# ArachnoMoto.net
KiCad netlist of a schematic drawn in EAGLE
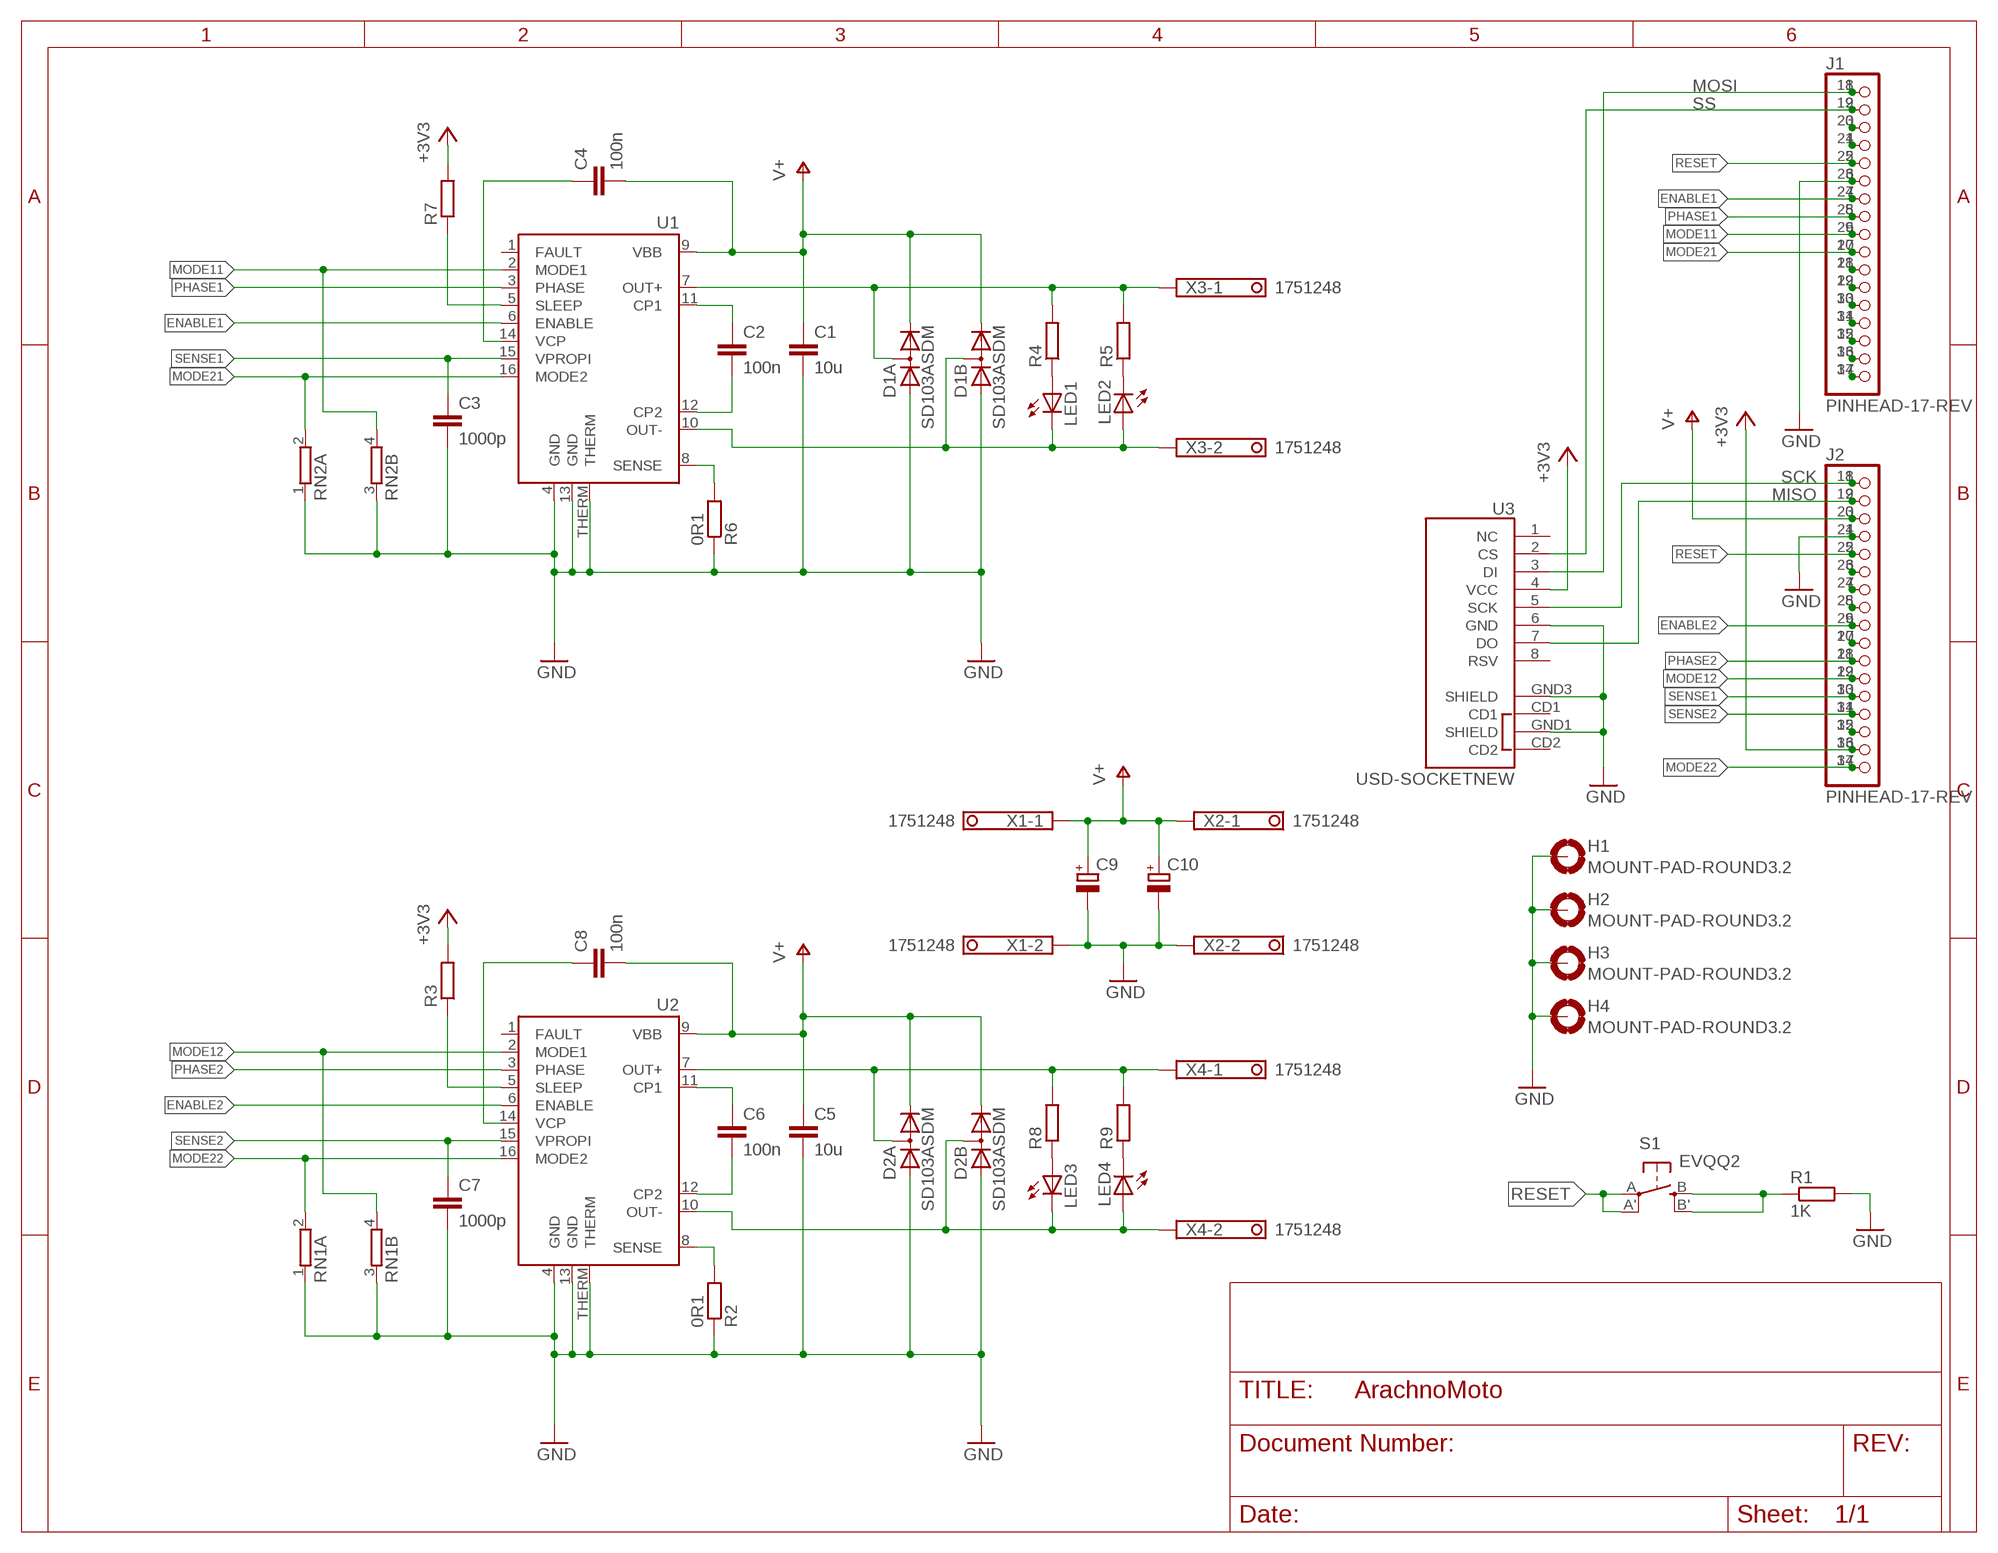
[diagram p0: schematic, sheet 1]

(export (version "E")
  (design (tool "Eeschema 10.0.6"))
  (components
    (comp (ref "C1")
      (value "10u")
      (footprint "eagle-import:C1210")
      (libsource (lib "eagle-import") (part "C-EUC1210"))
    )
    (comp (ref "C2")
      (value "100n")
      (footprint "eagle-import:C0603")
      (libsource (lib "eagle-import") (part "C-EUC0603"))
    )
    (comp (ref "C3")
      (value "1000p")
      (footprint "eagle-import:C0603")
      (libsource (lib "eagle-import") (part "C-EUC0603"))
    )
    (comp (ref "C4")
      (value "100n")
      (footprint "eagle-import:C0603")
      (libsource (lib "eagle-import") (part "C-EUC0603"))
    )
    (comp (ref "C5")
      (value "10u")
      (footprint "eagle-import:C1210")
      (libsource (lib "eagle-import") (part "C-EUC1210"))
    )
    (comp (ref "C6")
      (value "100n")
      (footprint "eagle-import:C0603")
      (libsource (lib "eagle-import") (part "C-EUC0603"))
    )
    (comp (ref "C7")
      (value "1000p")
      (footprint "eagle-import:C0603")
      (libsource (lib "eagle-import") (part "C-EUC0603"))
    )
    (comp (ref "C8")
      (value "100n")
      (footprint "eagle-import:C0603")
      (libsource (lib "eagle-import") (part "C-EUC0603"))
    )
    (comp (ref "C9")
      (value "CPOL-EUE5-10.5")
      (footprint "eagle-import:E5-10,5")
      (libsource (lib "eagle-import") (part "CPOL-EUE5-10.5"))
    )
    (comp (ref "C10")
      (value "CPOL-EUE5-10.5")
      (footprint "eagle-import:E5-10,5")
      (libsource (lib "eagle-import") (part "CPOL-EUE5-10.5"))
    )
    (comp (ref "D1")
      (value "SD103ASDM")
      (footprint "eagle-import:SOT26")
      (libsource (lib "eagle-import") (part "SD103ASDM"))
    )
    (comp (ref "D2")
      (value "SD103ASDM")
      (footprint "eagle-import:SOT26")
      (libsource (lib "eagle-import") (part "SD103ASDM"))
    )
    (comp (ref "H1")
      (value "MOUNT-PAD-ROUND3.2")
      (footprint "eagle-import:3,2-PAD")
      (libsource (lib "eagle-import") (part "MOUNT-PAD-ROUND3.2"))
    )
    (comp (ref "H2")
      (value "MOUNT-PAD-ROUND3.2")
      (footprint "eagle-import:3,2-PAD")
      (libsource (lib "eagle-import") (part "MOUNT-PAD-ROUND3.2"))
    )
    (comp (ref "H3")
      (value "MOUNT-PAD-ROUND3.2")
      (footprint "eagle-import:3,2-PAD")
      (libsource (lib "eagle-import") (part "MOUNT-PAD-ROUND3.2"))
    )
    (comp (ref "H4")
      (value "MOUNT-PAD-ROUND3.2")
      (footprint "eagle-import:3,2-PAD")
      (libsource (lib "eagle-import") (part "MOUNT-PAD-ROUND3.2"))
    )
    (comp (ref "J1")
      (value "PINHEAD-17-REV")
      (footprint "eagle-import:4UCONN-12573")
      (libsource (lib "eagle-import") (part "PINHEAD-17-REV"))
    )
    (comp (ref "J2")
      (value "PINHEAD-17-REV")
      (footprint "eagle-import:4UCONN-12573")
      (libsource (lib "eagle-import") (part "PINHEAD-17-REV"))
    )
    (comp (ref "LED1")
      (value "LEDCHIP-LED0603")
      (footprint "eagle-import:CHIP-LED0603")
      (libsource (lib "eagle-import") (part "LEDCHIP-LED0603"))
    )
    (comp (ref "LED2")
      (value "LEDCHIP-LED0603")
      (footprint "eagle-import:CHIP-LED0603")
      (libsource (lib "eagle-import") (part "LEDCHIP-LED0603"))
    )
    (comp (ref "LED3")
      (value "LEDCHIP-LED0603")
      (footprint "eagle-import:CHIP-LED0603")
      (libsource (lib "eagle-import") (part "LEDCHIP-LED0603"))
    )
    (comp (ref "LED4")
      (value "LEDCHIP-LED0603")
      (footprint "eagle-import:CHIP-LED0603")
      (libsource (lib "eagle-import") (part "LEDCHIP-LED0603"))
    )
    (comp (ref "R1")
      (value "1K")
      (footprint "eagle-import:R1206")
      (libsource (lib "eagle-import") (part "R-EU_R1206"))
    )
    (comp (ref "R2")
      (value "0R1")
      (footprint "eagle-import:R1206")
      (libsource (lib "eagle-import") (part "R-EU_R1206"))
    )
    (comp (ref "R3")
      (value "R-EU_R0603")
      (footprint "eagle-import:R0603")
      (libsource (lib "eagle-import") (part "R-EU_R0603"))
    )
    (comp (ref "R4")
      (value "R-EU_R0603")
      (footprint "eagle-import:R0603")
      (libsource (lib "eagle-import") (part "R-EU_R0603"))
    )
    (comp (ref "R5")
      (value "R-EU_R0603")
      (footprint "eagle-import:R0603")
      (libsource (lib "eagle-import") (part "R-EU_R0603"))
    )
    (comp (ref "R6")
      (value "0R1")
      (footprint "eagle-import:R1206")
      (libsource (lib "eagle-import") (part "R-EU_R1206"))
    )
    (comp (ref "R7")
      (value "R-EU_R0603")
      (footprint "eagle-import:R0603")
      (libsource (lib "eagle-import") (part "R-EU_R0603"))
    )
    (comp (ref "R8")
      (value "R-EU_R0603")
      (footprint "eagle-import:R0603")
      (libsource (lib "eagle-import") (part "R-EU_R0603"))
    )
    (comp (ref "R9")
      (value "R-EU_R0603")
      (footprint "eagle-import:R0603")
      (libsource (lib "eagle-import") (part "R-EU_R0603"))
    )
    (comp (ref "RN1")
      (value "4R-NCTS742C083")
      (footprint "eagle-import:CTS742C083-RES")
      (libsource (lib "eagle-import") (part "4R-NCTS742C083"))
    )
    (comp (ref "RN2")
      (value "4R-NCTS742C083")
      (footprint "eagle-import:CTS742C083-RES")
      (libsource (lib "eagle-import") (part "4R-NCTS742C083"))
    )
    (comp (ref "S1")
      (value "EVQQ2")
      (footprint "eagle-import:EVQ-Q2")
      (libsource (lib "eagle-import") (part "EVQQ2"))
    )
    (comp (ref "U1")
      (value "DRV8801")
      (footprint "eagle-import:HTSSOP16-PWP")
      (libsource (lib "eagle-import") (part "DRV8801"))
    )
    (comp (ref "U2")
      (value "DRV8801")
      (footprint "eagle-import:HTSSOP16-PWP")
      (libsource (lib "eagle-import") (part "DRV8801"))
    )
    (comp (ref "U3")
      (value "USD-SOCKETNEW")
      (footprint "eagle-import:MICRO-SD-SOCKET-PP")
      (libsource (lib "eagle-import") (part "USD-SOCKETNEW"))
    )
    (comp (ref "X1")
      (value "1751248")
      (footprint "eagle-import:1751248")
      (libsource (lib "eagle-import") (part "1751248"))
    )
    (comp (ref "X2")
      (value "1751248")
      (footprint "eagle-import:1751248")
      (libsource (lib "eagle-import") (part "1751248"))
    )
    (comp (ref "X3")
      (value "1751248")
      (footprint "eagle-import:1751248")
      (libsource (lib "eagle-import") (part "1751248"))
    )
    (comp (ref "X4")
      (value "1751248")
      (footprint "eagle-import:1751248")
      (libsource (lib "eagle-import") (part "1751248"))
    )
  )
  (nets
    (net (code "1") (name "+3V3") (class "Default")
      (node (ref "J2") (pin "16") (pinfunction "16_16") (pintype "passive"))
      (node (ref "J2") (pin "33") (pinfunction "33_33") (pintype "passive"))
      (node (ref "R3") (pin "2") (pinfunction "2_2") (pintype "passive"))
      (node (ref "R7") (pin "2") (pinfunction "2_2") (pintype "passive"))
      (node (ref "U3") (pin "4") (pinfunction "VCC_4") (pintype "bidirectional"))
    )
    (net (code "2") (name "/MISO") (class "Default")
      (node (ref "J2") (pin "19") (pinfunction "19_19") (pintype "passive"))
      (node (ref "J2") (pin "2") (pinfunction "2_2") (pintype "passive"))
      (node (ref "U3") (pin "7") (pinfunction "DO_7") (pintype "bidirectional"))
    )
    (net (code "3") (name "/MOSI") (class "Default")
      (node (ref "J1") (pin "1") (pinfunction "1_1") (pintype "passive"))
      (node (ref "J1") (pin "18") (pinfunction "18_18") (pintype "passive"))
      (node (ref "U3") (pin "3") (pinfunction "DI_3") (pintype "bidirectional"))
    )
    (net (code "4") (name "/SCK") (class "Default")
      (node (ref "J2") (pin "1") (pinfunction "1_1") (pintype "passive"))
      (node (ref "J2") (pin "18") (pinfunction "18_18") (pintype "passive"))
      (node (ref "U3") (pin "5") (pinfunction "SCK_5") (pintype "bidirectional"))
    )
    (net (code "5") (name "/SS") (class "Default")
      (node (ref "J1") (pin "19") (pinfunction "19_19") (pintype "passive"))
      (node (ref "J1") (pin "2") (pinfunction "2_2") (pintype "passive"))
      (node (ref "U3") (pin "2") (pinfunction "CS_2") (pintype "bidirectional"))
    )
    (net (code "6") (name "ENABLE1") (class "Default")
      (node (ref "J1") (pin "24") (pinfunction "24_24") (pintype "passive"))
      (node (ref "J1") (pin "7") (pinfunction "7_7") (pintype "passive"))
      (node (ref "U1") (pin "6") (pinfunction "ENABLE_6") (pintype "bidirectional"))
    )
    (net (code "7") (name "ENABLE2") (class "Default")
      (node (ref "J2") (pin "26") (pinfunction "26_26") (pintype "passive"))
      (node (ref "J2") (pin "9") (pinfunction "9_9") (pintype "passive"))
      (node (ref "U2") (pin "6") (pinfunction "ENABLE_6") (pintype "bidirectional"))
    )
    (net (code "8") (name "GND") (class "Default")
      (node (ref "C1") (pin "2") (pinfunction "2_2") (pintype "passive"))
      (node (ref "C10") (pin "-") (pinfunction "-_-") (pintype "passive"))
      (node (ref "C3") (pin "2") (pinfunction "2_2") (pintype "passive"))
      (node (ref "C5") (pin "2") (pinfunction "2_2") (pintype "passive"))
      (node (ref "C7") (pin "2") (pinfunction "2_2") (pintype "passive"))
      (node (ref "C9") (pin "-") (pinfunction "-_-") (pintype "passive"))
      (node (ref "D1") (pin "3") (pinfunction "A_3") (pintype "passive"))
      (node (ref "D1") (pin "6") (pinfunction "A_6") (pintype "passive"))
      (node (ref "D2") (pin "3") (pinfunction "A_3") (pintype "passive"))
      (node (ref "D2") (pin "6") (pinfunction "A_6") (pintype "passive"))
      (node (ref "H1") (pin "B3,2") (pinfunction "MOUNT_B3,2") (pintype "passive"))
      (node (ref "H2") (pin "B3,2") (pinfunction "MOUNT_B3,2") (pintype "passive"))
      (node (ref "H3") (pin "B3,2") (pinfunction "MOUNT_B3,2") (pintype "passive"))
      (node (ref "H4") (pin "B3,2") (pinfunction "MOUNT_B3,2") (pintype "passive"))
      (node (ref "J1") (pin "23") (pinfunction "23_23") (pintype "passive"))
      (node (ref "J1") (pin "6") (pinfunction "6_6") (pintype "passive"))
      (node (ref "J2") (pin "21") (pinfunction "21_21") (pintype "passive"))
      (node (ref "J2") (pin "4") (pinfunction "4_4") (pintype "passive"))
      (node (ref "R1") (pin "2") (pinfunction "2_2") (pintype "passive"))
      (node (ref "R2") (pin "1") (pinfunction "1_1") (pintype "passive"))
      (node (ref "R6") (pin "1") (pinfunction "1_1") (pintype "passive"))
      (node (ref "RN1") (pin "1") (pinfunction "1_1") (pintype "passive"))
      (node (ref "RN1") (pin "3") (pinfunction "1_3") (pintype "passive"))
      (node (ref "RN2") (pin "1") (pinfunction "1_1") (pintype "passive"))
      (node (ref "RN2") (pin "3") (pinfunction "1_3") (pintype "passive"))
      (node (ref "U1") (pin "13") (pinfunction "GND_13") (pintype "bidirectional"))
      (node (ref "U1") (pin "4") (pinfunction "GND_4") (pintype "bidirectional"))
      (node (ref "U1") (pin "THERM") (pinfunction "THERM_THERM") (pintype "bidirectional"))
      (node (ref "U2") (pin "13") (pinfunction "GND_13") (pintype "bidirectional"))
      (node (ref "U2") (pin "4") (pinfunction "GND_4") (pintype "bidirectional"))
      (node (ref "U2") (pin "THERM") (pinfunction "THERM_THERM") (pintype "bidirectional"))
      (node (ref "U3") (pin "6") (pinfunction "GND_6") (pintype "bidirectional"))
      (node (ref "U3") (pin "GND1") (pinfunction "SHIELD_GND1") (pintype "bidirectional"))
      (node (ref "U3") (pin "GND3") (pinfunction "SHIELD_GND3") (pintype "bidirectional"))
      (node (ref "X1") (pin "2") (pinfunction "K_2") (pintype "passive"))
      (node (ref "X2") (pin "2") (pinfunction "K_2") (pintype "passive"))
    )
    (net (code "9") (name "MODE11") (class "Default")
      (node (ref "J1") (pin "26") (pinfunction "26_26") (pintype "passive"))
      (node (ref "J1") (pin "9") (pinfunction "9_9") (pintype "passive"))
      (node (ref "RN2") (pin "4") (pinfunction "2_4") (pintype "passive"))
      (node (ref "U1") (pin "2") (pinfunction "MODE1_2") (pintype "bidirectional"))
    )
    (net (code "10") (name "MODE12") (class "Default")
      (node (ref "J2") (pin "12") (pinfunction "12_12") (pintype "passive"))
      (node (ref "J2") (pin "29") (pinfunction "29_29") (pintype "passive"))
      (node (ref "RN1") (pin "4") (pinfunction "2_4") (pintype "passive"))
      (node (ref "U2") (pin "2") (pinfunction "MODE1_2") (pintype "bidirectional"))
    )
    (net (code "11") (name "MODE21") (class "Default")
      (node (ref "J1") (pin "10") (pinfunction "10_10") (pintype "passive"))
      (node (ref "J1") (pin "27") (pinfunction "27_27") (pintype "passive"))
      (node (ref "RN2") (pin "2") (pinfunction "2_2") (pintype "passive"))
      (node (ref "U1") (pin "16") (pinfunction "MODE2_16") (pintype "bidirectional"))
    )
    (net (code "12") (name "MODE22") (class "Default")
      (node (ref "J2") (pin "17") (pinfunction "17_17") (pintype "passive"))
      (node (ref "J2") (pin "34") (pinfunction "34_34") (pintype "passive"))
      (node (ref "RN1") (pin "2") (pinfunction "2_2") (pintype "passive"))
      (node (ref "U2") (pin "16") (pinfunction "MODE2_16") (pintype "bidirectional"))
    )
    (net (code "13") (name "Net-(D1A-AC)") (class "Default")
      (node (ref "D1") (pin "4") (pinfunction "AC_4") (pintype "passive"))
      (node (ref "R4") (pin "2") (pinfunction "2_2") (pintype "passive"))
      (node (ref "R5") (pin "2") (pinfunction "2_2") (pintype "passive"))
      (node (ref "U1") (pin "7") (pinfunction "OUT+_7") (pintype "bidirectional"))
      (node (ref "X3") (pin "1") (pinfunction "K_1") (pintype "passive"))
    )
    (net (code "14") (name "Net-(D1B-AC)") (class "Default")
      (node (ref "D1") (pin "1") (pinfunction "AC_1") (pintype "passive"))
      (node (ref "LED1") (pin "C") (pinfunction "C_C") (pintype "passive"))
      (node (ref "LED2") (pin "A") (pinfunction "A_A") (pintype "passive"))
      (node (ref "U1") (pin "10") (pinfunction "OUT-_10") (pintype "bidirectional"))
      (node (ref "X3") (pin "2") (pinfunction "K_2") (pintype "passive"))
    )
    (net (code "15") (name "Net-(D2A-AC)") (class "Default")
      (node (ref "D2") (pin "4") (pinfunction "AC_4") (pintype "passive"))
      (node (ref "R8") (pin "2") (pinfunction "2_2") (pintype "passive"))
      (node (ref "R9") (pin "2") (pinfunction "2_2") (pintype "passive"))
      (node (ref "U2") (pin "7") (pinfunction "OUT+_7") (pintype "bidirectional"))
      (node (ref "X4") (pin "1") (pinfunction "K_1") (pintype "passive"))
    )
    (net (code "16") (name "Net-(D2B-AC)") (class "Default")
      (node (ref "D2") (pin "1") (pinfunction "AC_1") (pintype "passive"))
      (node (ref "LED3") (pin "C") (pinfunction "C_C") (pintype "passive"))
      (node (ref "LED4") (pin "A") (pinfunction "A_A") (pintype "passive"))
      (node (ref "U2") (pin "10") (pinfunction "OUT-_10") (pintype "bidirectional"))
      (node (ref "X4") (pin "2") (pinfunction "K_2") (pintype "passive"))
    )
    (net (code "17") (name "Net-(J1-Pad11)") (class "Default")
      (node (ref "J1") (pin "11") (pinfunction "11_11") (pintype "passive"))
      (node (ref "J1") (pin "28") (pinfunction "28_28") (pintype "passive"))
    )
    (net (code "18") (name "Net-(J1-Pad12)") (class "Default")
      (node (ref "J1") (pin "12") (pinfunction "12_12") (pintype "passive"))
      (node (ref "J1") (pin "29") (pinfunction "29_29") (pintype "passive"))
    )
    (net (code "19") (name "Net-(J1-Pad13)") (class "Default")
      (node (ref "J1") (pin "13") (pinfunction "13_13") (pintype "passive"))
      (node (ref "J1") (pin "30") (pinfunction "30_30") (pintype "passive"))
    )
    (net (code "20") (name "Net-(J1-Pad14)") (class "Default")
      (node (ref "J1") (pin "14") (pinfunction "14_14") (pintype "passive"))
      (node (ref "J1") (pin "31") (pinfunction "31_31") (pintype "passive"))
    )
    (net (code "21") (name "Net-(J1-Pad15)") (class "Default")
      (node (ref "J1") (pin "15") (pinfunction "15_15") (pintype "passive"))
      (node (ref "J1") (pin "32") (pinfunction "32_32") (pintype "passive"))
    )
    (net (code "22") (name "Net-(J1-Pad16)") (class "Default")
      (node (ref "J1") (pin "16") (pinfunction "16_16") (pintype "passive"))
      (node (ref "J1") (pin "33") (pinfunction "33_33") (pintype "passive"))
    )
    (net (code "23") (name "Net-(J1-Pad17)") (class "Default")
      (node (ref "J1") (pin "17") (pinfunction "17_17") (pintype "passive"))
      (node (ref "J1") (pin "34") (pinfunction "34_34") (pintype "passive"))
    )
    (net (code "24") (name "Net-(J1-Pad20)") (class "Default")
      (node (ref "J1") (pin "20") (pinfunction "20_20") (pintype "passive"))
      (node (ref "J1") (pin "3") (pinfunction "3_3") (pintype "passive"))
    )
    (net (code "25") (name "Net-(J1-Pad21)") (class "Default")
      (node (ref "J1") (pin "21") (pinfunction "21_21") (pintype "passive"))
      (node (ref "J1") (pin "4") (pinfunction "4_4") (pintype "passive"))
    )
    (net (code "26") (name "Net-(J2-Pad10)") (class "Default")
      (node (ref "J2") (pin "10") (pinfunction "10_10") (pintype "passive"))
      (node (ref "J2") (pin "27") (pinfunction "27_27") (pintype "passive"))
    )
    (net (code "27") (name "Net-(J2-Pad15)") (class "Default")
      (node (ref "J2") (pin "15") (pinfunction "15_15") (pintype "passive"))
      (node (ref "J2") (pin "32") (pinfunction "32_32") (pintype "passive"))
    )
    (net (code "28") (name "Net-(J2-Pad23)") (class "Default")
      (node (ref "J2") (pin "23") (pinfunction "23_23") (pintype "passive"))
      (node (ref "J2") (pin "6") (pinfunction "6_6") (pintype "passive"))
    )
    (net (code "29") (name "Net-(J2-Pad24)") (class "Default")
      (node (ref "J2") (pin "24") (pinfunction "24_24") (pintype "passive"))
      (node (ref "J2") (pin "7") (pinfunction "7_7") (pintype "passive"))
    )
    (net (code "30") (name "Net-(J2-Pad25)") (class "Default")
      (node (ref "J2") (pin "25") (pinfunction "25_25") (pintype "passive"))
      (node (ref "J2") (pin "8") (pinfunction "8_8") (pintype "passive"))
    )
    (net (code "31") (name "Net-(LED1-PadA)") (class "Default")
      (node (ref "LED1") (pin "A") (pinfunction "A_A") (pintype "passive"))
      (node (ref "R4") (pin "1") (pinfunction "1_1") (pintype "passive"))
    )
    (net (code "32") (name "Net-(LED2-PadC)") (class "Default")
      (node (ref "LED2") (pin "C") (pinfunction "C_C") (pintype "passive"))
      (node (ref "R5") (pin "1") (pinfunction "1_1") (pintype "passive"))
    )
    (net (code "33") (name "Net-(LED3-PadA)") (class "Default")
      (node (ref "LED3") (pin "A") (pinfunction "A_A") (pintype "passive"))
      (node (ref "R8") (pin "1") (pinfunction "1_1") (pintype "passive"))
    )
    (net (code "34") (name "Net-(LED4-PadC)") (class "Default")
      (node (ref "LED4") (pin "C") (pinfunction "C_C") (pintype "passive"))
      (node (ref "R9") (pin "1") (pinfunction "1_1") (pintype "passive"))
    )
    (net (code "35") (name "Net-(S1-S)") (class "Default")
      (node (ref "R1") (pin "1") (pinfunction "1_1") (pintype "passive"))
      (node (ref "S1") (pin "B") (pinfunction "S_B") (pintype "passive"))
      (node (ref "S1") (pin "B'") (pinfunction "S1_B'") (pintype "passive"))
    )
    (net (code "36") (name "Net-(U1-CP1)") (class "Default")
      (node (ref "C2") (pin "1") (pinfunction "1_1") (pintype "passive"))
      (node (ref "U1") (pin "11") (pinfunction "CP1_11") (pintype "bidirectional"))
    )
    (net (code "37") (name "Net-(U1-CP2)") (class "Default")
      (node (ref "C2") (pin "2") (pinfunction "2_2") (pintype "passive"))
      (node (ref "U1") (pin "12") (pinfunction "CP2_12") (pintype "bidirectional"))
    )
    (net (code "38") (name "Net-(U1-SENSE)") (class "Default")
      (node (ref "R6") (pin "2") (pinfunction "2_2") (pintype "passive"))
      (node (ref "U1") (pin "8") (pinfunction "SENSE_8") (pintype "bidirectional"))
    )
    (net (code "39") (name "Net-(U1-SLEEP)") (class "Default")
      (node (ref "R7") (pin "1") (pinfunction "1_1") (pintype "passive"))
      (node (ref "U1") (pin "5") (pinfunction "SLEEP_5") (pintype "bidirectional"))
    )
    (net (code "40") (name "Net-(U1-VCP)") (class "Default")
      (node (ref "C4") (pin "1") (pinfunction "1_1") (pintype "passive"))
      (node (ref "U1") (pin "14") (pinfunction "VCP_14") (pintype "bidirectional"))
    )
    (net (code "41") (name "Net-(U2-CP1)") (class "Default")
      (node (ref "C6") (pin "1") (pinfunction "1_1") (pintype "passive"))
      (node (ref "U2") (pin "11") (pinfunction "CP1_11") (pintype "bidirectional"))
    )
    (net (code "42") (name "Net-(U2-CP2)") (class "Default")
      (node (ref "C6") (pin "2") (pinfunction "2_2") (pintype "passive"))
      (node (ref "U2") (pin "12") (pinfunction "CP2_12") (pintype "bidirectional"))
    )
    (net (code "43") (name "Net-(U2-SENSE)") (class "Default")
      (node (ref "R2") (pin "2") (pinfunction "2_2") (pintype "passive"))
      (node (ref "U2") (pin "8") (pinfunction "SENSE_8") (pintype "bidirectional"))
    )
    (net (code "44") (name "Net-(U2-SLEEP)") (class "Default")
      (node (ref "R3") (pin "1") (pinfunction "1_1") (pintype "passive"))
      (node (ref "U2") (pin "5") (pinfunction "SLEEP_5") (pintype "bidirectional"))
    )
    (net (code "45") (name "Net-(U2-VCP)") (class "Default")
      (node (ref "C8") (pin "1") (pinfunction "1_1") (pintype "passive"))
      (node (ref "U2") (pin "14") (pinfunction "VCP_14") (pintype "bidirectional"))
    )
    (net (code "46") (name "PHASE1") (class "Default")
      (node (ref "J1") (pin "25") (pinfunction "25_25") (pintype "passive"))
      (node (ref "J1") (pin "8") (pinfunction "8_8") (pintype "passive"))
      (node (ref "U1") (pin "3") (pinfunction "PHASE_3") (pintype "bidirectional"))
    )
    (net (code "47") (name "PHASE2") (class "Default")
      (node (ref "J2") (pin "11") (pinfunction "11_11") (pintype "passive"))
      (node (ref "J2") (pin "28") (pinfunction "28_28") (pintype "passive"))
      (node (ref "U2") (pin "3") (pinfunction "PHASE_3") (pintype "bidirectional"))
    )
    (net (code "48") (name "RESET") (class "Default")
      (node (ref "J1") (pin "22") (pinfunction "22_22") (pintype "passive"))
      (node (ref "J1") (pin "5") (pinfunction "5_5") (pintype "passive"))
      (node (ref "J2") (pin "22") (pinfunction "22_22") (pintype "passive"))
      (node (ref "J2") (pin "5") (pinfunction "5_5") (pintype "passive"))
      (node (ref "S1") (pin "A") (pinfunction "P_A") (pintype "passive"))
      (node (ref "S1") (pin "A'") (pinfunction "P1_A'") (pintype "passive"))
    )
    (net (code "49") (name "SENSE1") (class "Default")
      (node (ref "C3") (pin "1") (pinfunction "1_1") (pintype "passive"))
      (node (ref "J2") (pin "13") (pinfunction "13_13") (pintype "passive"))
      (node (ref "J2") (pin "30") (pinfunction "30_30") (pintype "passive"))
      (node (ref "U1") (pin "15") (pinfunction "VPROPI_15") (pintype "bidirectional"))
    )
    (net (code "50") (name "SENSE2") (class "Default")
      (node (ref "C7") (pin "1") (pinfunction "1_1") (pintype "passive"))
      (node (ref "J2") (pin "14") (pinfunction "14_14") (pintype "passive"))
      (node (ref "J2") (pin "31") (pinfunction "31_31") (pintype "passive"))
      (node (ref "U2") (pin "15") (pinfunction "VPROPI_15") (pintype "bidirectional"))
    )
    (net (code "51") (name "V+") (class "Default")
      (node (ref "C1") (pin "1") (pinfunction "1_1") (pintype "passive"))
      (node (ref "C10") (pin "+") (pinfunction "+_+") (pintype "passive"))
      (node (ref "C4") (pin "2") (pinfunction "2_2") (pintype "passive"))
      (node (ref "C5") (pin "1") (pinfunction "1_1") (pintype "passive"))
      (node (ref "C8") (pin "2") (pinfunction "2_2") (pintype "passive"))
      (node (ref "C9") (pin "+") (pinfunction "+_+") (pintype "passive"))
      (node (ref "D1") (pin "2") (pinfunction "C_2") (pintype "passive"))
      (node (ref "D1") (pin "5") (pinfunction "C_5") (pintype "passive"))
      (node (ref "D2") (pin "2") (pinfunction "C_2") (pintype "passive"))
      (node (ref "D2") (pin "5") (pinfunction "C_5") (pintype "passive"))
      (node (ref "J2") (pin "20") (pinfunction "20_20") (pintype "passive"))
      (node (ref "J2") (pin "3") (pinfunction "3_3") (pintype "passive"))
      (node (ref "U1") (pin "9") (pinfunction "VBB_9") (pintype "bidirectional"))
      (node (ref "U2") (pin "9") (pinfunction "VBB_9") (pintype "bidirectional"))
      (node (ref "X1") (pin "1") (pinfunction "K_1") (pintype "passive"))
      (node (ref "X2") (pin "1") (pinfunction "K_1") (pintype "passive"))
    )
    (net (code "52") (name "unconnected-(U1-FAULT-Pad1)") (class "Default")
      (node (ref "U1") (pin "1") (pinfunction "FAULT_1") (pintype "bidirectional"))
    )
    (net (code "53") (name "unconnected-(U2-FAULT-Pad1)") (class "Default")
      (node (ref "U2") (pin "1") (pinfunction "FAULT_1") (pintype "bidirectional"))
    )
    (net (code "54") (name "unconnected-(U3-NC-Pad1)") (class "Default")
      (node (ref "U3") (pin "1") (pinfunction "NC_1") (pintype "bidirectional"))
    )
    (net (code "55") (name "unconnected-(U3-PadCD1)") (class "Default")
      (node (ref "U3") (pin "CD1") (pinfunction "CD1_CD1") (pintype "bidirectional"))
    )
    (net (code "56") (name "unconnected-(U3-PadCD2)") (class "Default")
      (node (ref "U3") (pin "CD2") (pinfunction "CD2_CD2") (pintype "bidirectional"))
    )
    (net (code "57") (name "unconnected-(U3-RSV-Pad8)") (class "Default")
      (node (ref "U3") (pin "8") (pinfunction "RSV_8") (pintype "bidirectional"))
    )
  )
)
